# Atom-N.net
KiCad netlist of a schematic drawn in Altium Designer
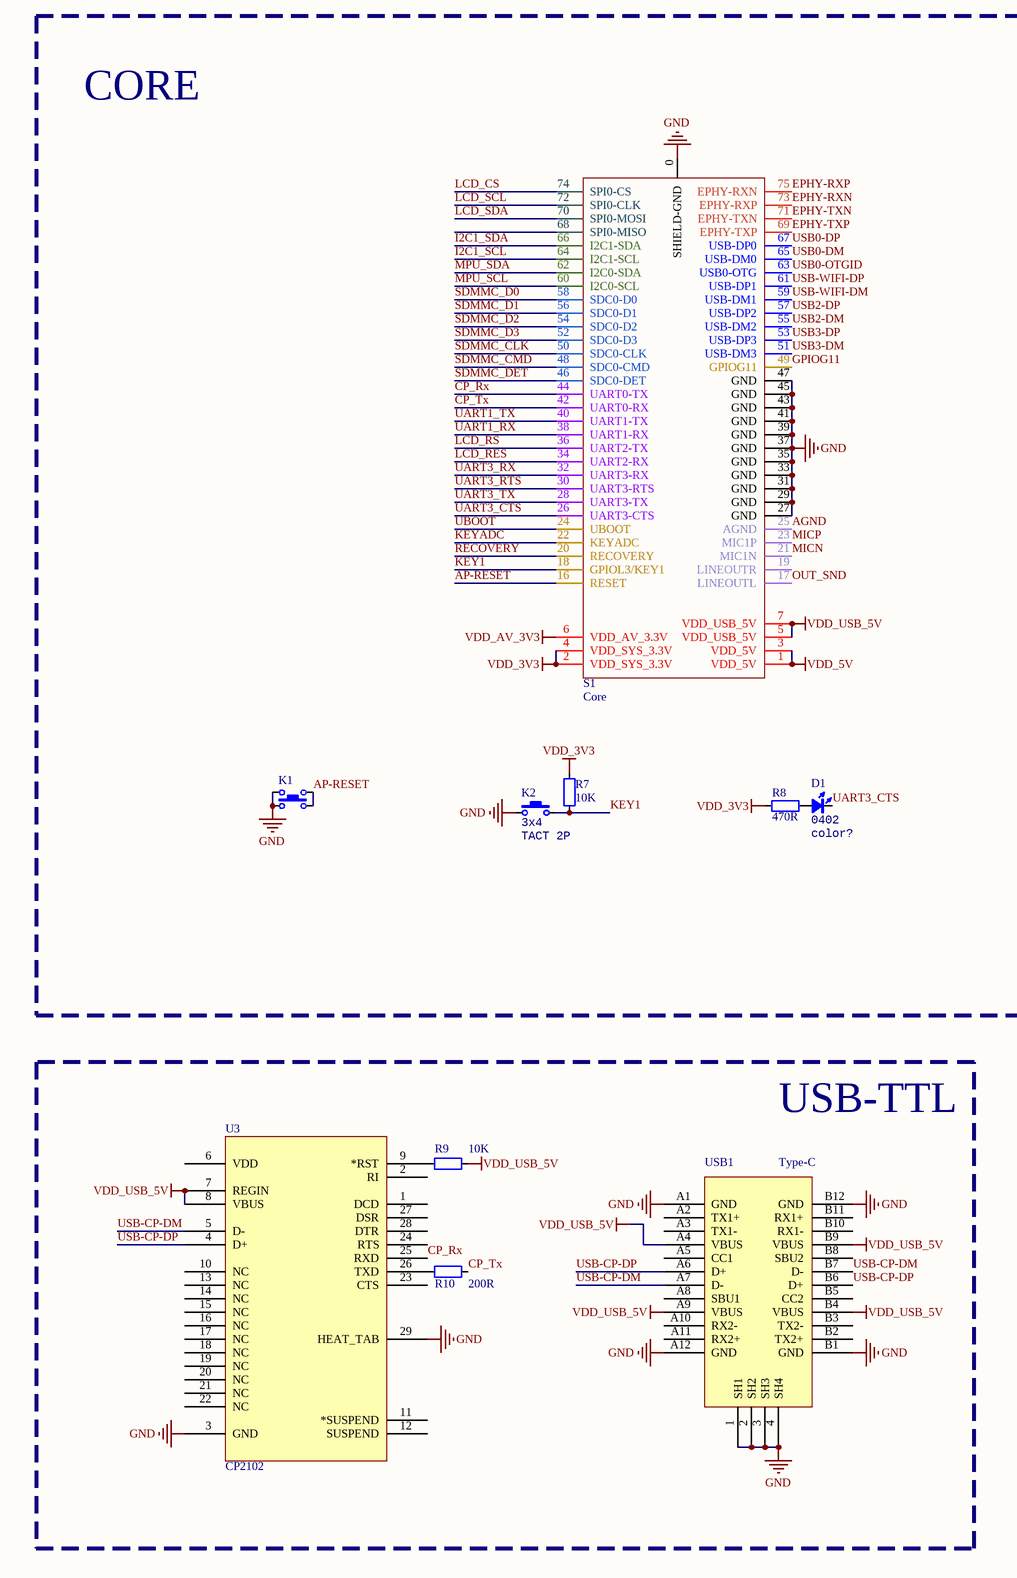
[diagram p0: Atom-N.SchDoc, left]
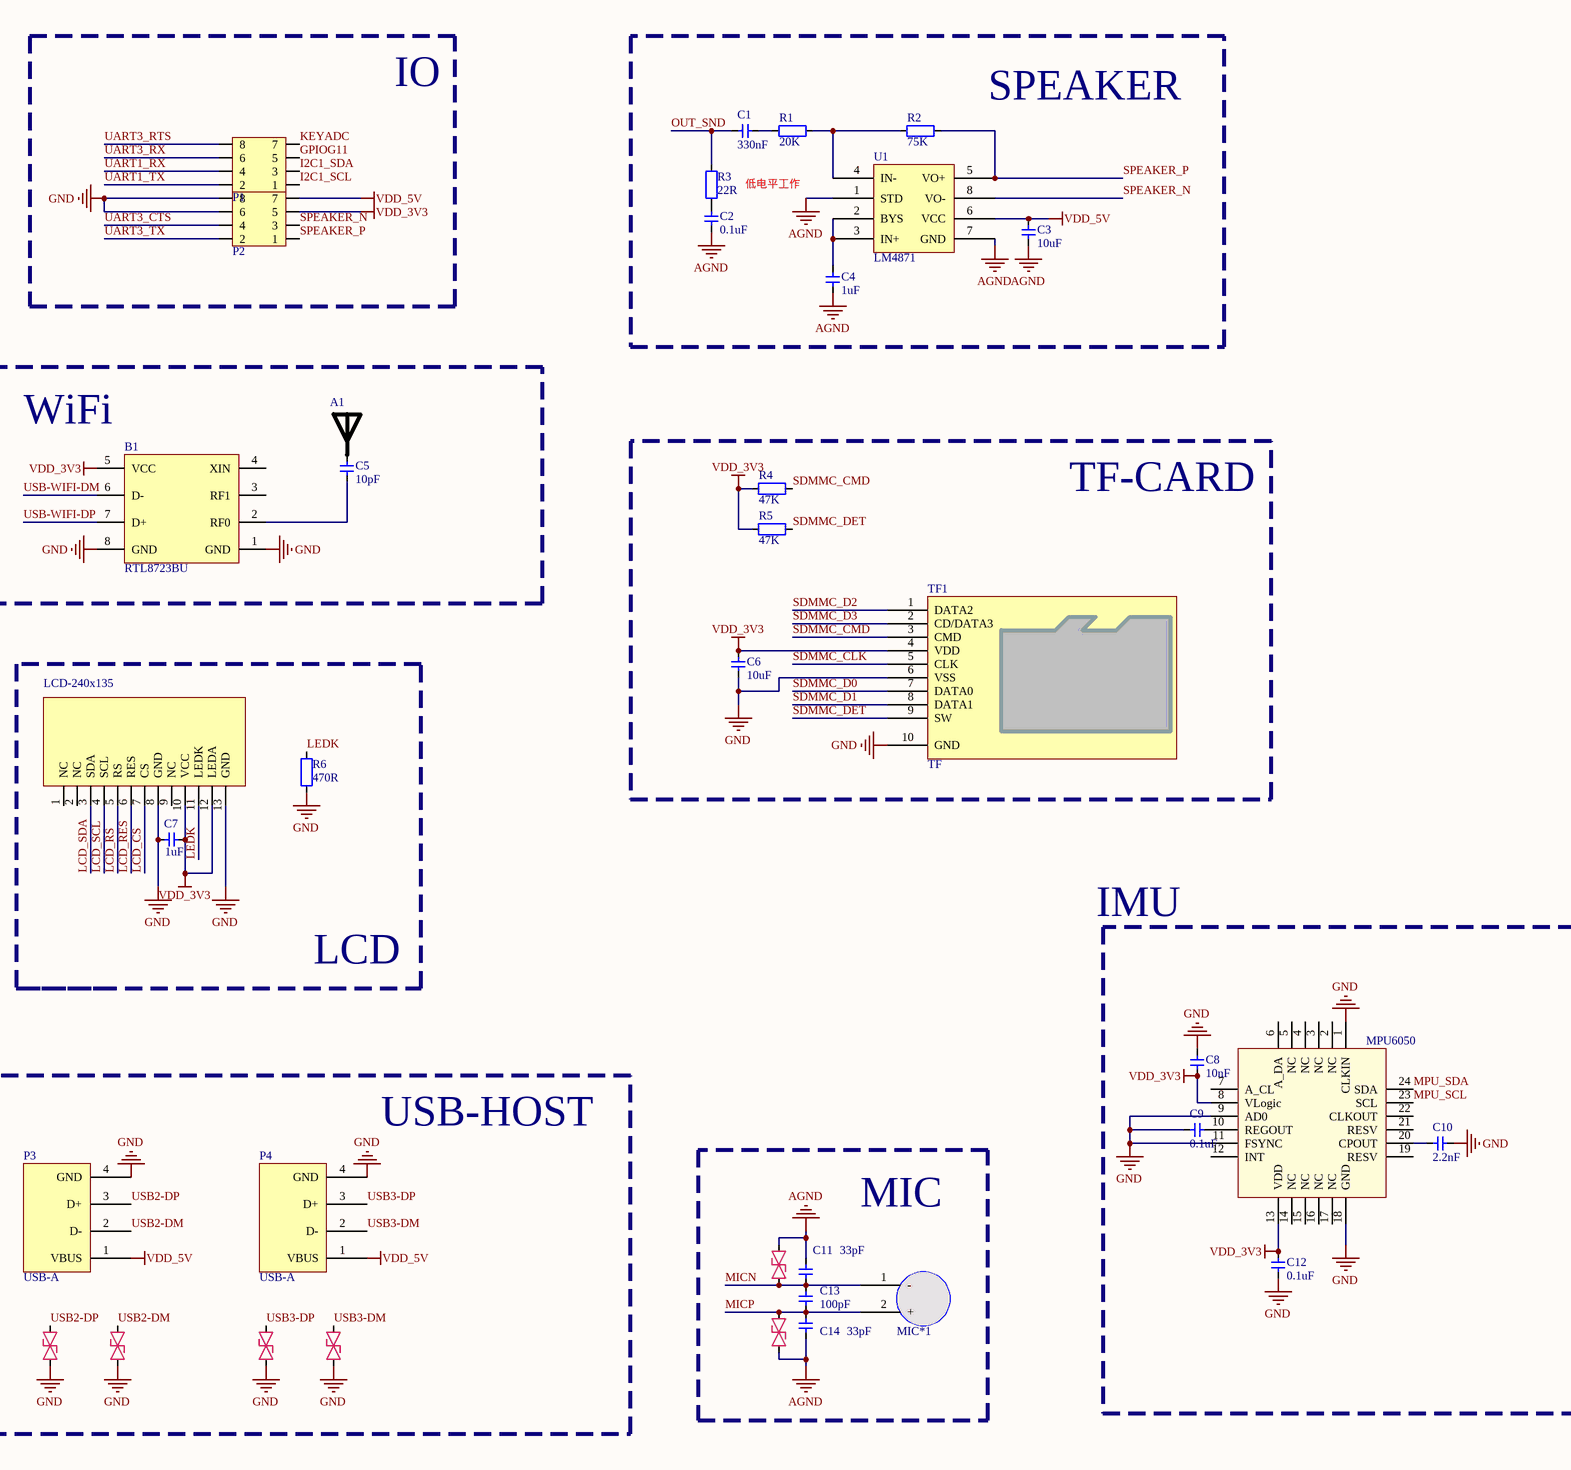
[diagram p1: Atom-N.SchDoc, right]

(export (version "E")
  (design (tool "Eeschema 10.0.6"))
  (components
    (comp (ref "1")
      (value "LCD-240x135")
      (footprint "LCD-240x135")
      (description "显示屏")
      (libsource (lib "MyPcbLib") (part "LCD-240x135"))
    )
    (comp (ref "A1")
      (value "RAINSUN")
      (footprint "ANT-Rainsun-AN5120")
      (libsource (lib "MyPcbLib") (part "ANT-Rainsun-AP5120"))
    )
    (comp (ref "B1")
      (value "RTL8723BU")
      (footprint "USB-WiFI-BT-RTL8723BU")
      (libsource (lib "MyPcbLib") (part "USB-WiFi-BT-RTL8723BU"))
    )
    (comp (ref "C1")
      (value "330nF")
      (footprint "0603-CAP")
      (description "Capacitor")
      (libsource (lib "MyPcbLib") (part "电容-0603"))
    )
    (comp (ref "C2")
      (value "0.1uF")
      (footprint "CAP_0402")
      (description "Capacitor")
      (libsource (lib "MyPcbLib") (part "电容-0402"))
    )
    (comp (ref "C3")
      (value "10uF")
      (footprint "CAP_0402")
      (description "Capacitor")
      (libsource (lib "MyPcbLib") (part "电容-0402"))
    )
    (comp (ref "C4")
      (value "1uF")
      (footprint "CAP_0402")
      (description "Capacitor")
      (libsource (lib "MyPcbLib") (part "电容-0402"))
    )
    (comp (ref "C5")
      (value "10pF")
      (footprint "CAP_0402")
      (description "Capacitor")
      (libsource (lib "MyPcbLib") (part "电容-0402"))
    )
    (comp (ref "C6")
      (value "10uF")
      (footprint "CAP_0402")
      (description "Capacitor")
      (libsource (lib "MyPcbLib") (part "电容-0402"))
    )
    (comp (ref "C7")
      (value "1uF")
      (footprint "CAP_0402")
      (description "Capacitor")
      (libsource (lib "MyPcbLib") (part "电容-0402"))
    )
    (comp (ref "C8")
      (value "10nF")
      (footprint "CAP_0402")
      (description "Capacitor")
      (libsource (lib "MyPcbLib") (part "电容-0402"))
    )
    (comp (ref "C9")
      (value "0.1uF")
      (footprint "CAP_0402")
      (description "Capacitor")
      (libsource (lib "MyPcbLib") (part "电容-0402"))
    )
    (comp (ref "C10")
      (value "2.2nF")
      (footprint "CAP_0402")
      (description "Capacitor")
      (libsource (lib "MyPcbLib") (part "电容-0402"))
    )
    (comp (ref "C11")
      (value "33pF")
      (footprint "CAP_0402")
      (description "Capacitor")
      (libsource (lib "MyPcbLib") (part "电容-0402"))
    )
    (comp (ref "C12")
      (value "0.1uF")
      (footprint "CAP_0402")
      (description "Capacitor")
      (libsource (lib "MyPcbLib") (part "电容-0402"))
    )
    (comp (ref "C13")
      (value "100pF")
      (footprint "CAP_0402")
      (description "Capacitor")
      (libsource (lib "MyPcbLib") (part "电容-0402"))
    )
    (comp (ref "C14")
      (value "33pF")
      (footprint "CAP_0402")
      (description "Capacitor")
      (libsource (lib "MyPcbLib") (part "电容-0402"))
    )
    (comp (ref "D1")
      (value "color?")
      (footprint "LED_0402_RED")
      (description "LED")
      (fields (field (name "TYPE") "0402"))
      (libsource (lib "KitSprout") (part "LED_0402"))
    )
    (comp (ref "ESD-1")
      (value "ESD-0402")
      (footprint "ESD-0402")
      (description "ESD")
      (libsource (lib "MyPcbLib") (part "ESD-0402"))
    )
    (comp (ref "ESD-2")
      (value "ESD-0402")
      (footprint "ESD-0402")
      (description "ESD")
      (libsource (lib "MyPcbLib") (part "ESD-0402"))
    )
    (comp (ref "ESD-3")
      (value "ESD-0402")
      (footprint "ESD-0402")
      (description "ESD")
      (libsource (lib "MyPcbLib") (part "ESD-0402"))
    )
    (comp (ref "ESD-4")
      (value "ESD-0402")
      (footprint "ESD-0402")
      (description "ESD")
      (libsource (lib "MyPcbLib") (part "ESD-0402"))
    )
    (comp (ref "ESD-5")
      (value "ESD-0402")
      (footprint "ESD-0402")
      (description "ESD")
      (libsource (lib "MyPcbLib") (part "ESD-0402"))
    )
    (comp (ref "ESD-6")
      (value "ESD-0402")
      (footprint "ESD-0402")
      (description "ESD")
      (libsource (lib "MyPcbLib") (part "ESD-0402"))
    )
    (comp (ref "K1")
      (value "TACT 4P")
      (footprint "ButtonTACT_3.5*3.55_90")
      (description "Button")
      (libsource (lib "KitSprout") (part "ButtonTACT"))
    )
    (comp (ref "K2")
      (value "3x4")
      (footprint "ButtonTACT_3x4x2_180")
      (description "Button")
      (fields (field (name "TYPE") "TACT 2P") (field (name "Comment") "TACT 2P"))
      (libsource (lib "KitSprout") (part "ButtonTACT_3x4x2_180"))
    )
    (comp (ref "MIC*1") (value "MIC*") (footprint "MIC-SMT") (libsource (lib "mLib") (part "MIC")))
    (comp (ref "P1")
      (value "HDR2x4_2.54")
      (footprint "HDR2X4_2.0_180H")
      (description "Header")
      (libsource (lib "mLib") (part "HDR2x4_2.54"))
    )
    (comp (ref "P2")
      (value "HDR2x4_2.54")
      (footprint "HDR2X4_2.0_180H")
      (description "Header")
      (libsource (lib "mLib") (part "HDR2x4_2.54"))
    )
    (comp (ref "P3") (value "USB-A") (footprint "USB-Short") (libsource (lib "MyPcbLib") (part "USB-A")))
    (comp (ref "P4") (value "USB-A") (footprint "USB-Short") (libsource (lib "MyPcbLib") (part "USB-A")))
    (comp (ref "R1")
      (value "20K")
      (footprint "RES_0402")
      (description "Resistor")
      (libsource (lib "") (part "电阻-0402_1"))
    )
    (comp (ref "R2")
      (value "75K")
      (footprint "RES_0402")
      (description "Resistor")
      (libsource (lib "") (part "电阻-0402_1"))
    )
    (comp (ref "R3")
      (value "22R")
      (footprint "RES_0402")
      (description "Resistor")
      (libsource (lib "") (part "电阻-0402_2"))
    )
    (comp (ref "R4")
      (value "47K")
      (footprint "RES_0402")
      (description "Resistor")
      (libsource (lib "") (part "电阻-0402_1"))
    )
    (comp (ref "R5")
      (value "47K")
      (footprint "RES_0402")
      (description "Resistor")
      (libsource (lib "") (part "电阻-0402_1"))
    )
    (comp (ref "R6")
      (value "470R")
      (footprint "RES_0402")
      (description "Resistor")
      (libsource (lib "") (part "电阻-0402_2"))
    )
    (comp (ref "R7")
      (value "10K")
      (footprint "RES_0402")
      (description "Resistor")
      (libsource (lib "") (part "电阻-0402_2"))
    )
    (comp (ref "R8")
      (value "470R")
      (footprint "RES_0402")
      (description "Resistor")
      (libsource (lib "MyPcbLib") (part "电阻-0402"))
    )
    (comp (ref "R9")
      (value "10K")
      (footprint "RES_0402")
      (description "Resistor")
      (libsource (lib "MyPcbLib") (part "电阻-0402"))
    )
    (comp (ref "R10")
      (value "200R")
      (footprint "RES_0402")
      (description "Resistor")
      (libsource (lib "MyPcbLib") (part "电阻-0402"))
    )
    (comp (ref "S1")
      (value "Core")
      (footprint "QUANTUM-QUARK-N")
      (libsource (lib "SOM") (part "Quantum-Quark-N"))
    )
    (comp (ref "TF1")
      (value "TF")
      (footprint "TF-SOCKET - short")
      (description "8脚自弹")
      (libsource (lib "MyPcbLib") (part "TF卡座"))
    )
    (comp (ref "U1") (value "LM4871") (footprint "MSOP-8") (libsource (lib "mLib") (part "LM4871")))
    (comp (ref "U2")
      (value "MPU6050")
      (footprint "QFN-24")
      (description "六轴传感器")
      (libsource (lib "mLib") (part "MPU6050"))
    )
    (comp (ref "U3")
      (value "CP2102")
      (footprint "QFN-28")
      (description "USB转TTL")
      (libsource (lib "mLib") (part "CP2102"))
    )
    (comp (ref "USB1")
      (value "Type-C")
      (footprint "Type-C-TOP")
      (libsource (lib "MyPcbLib") (part "USB-Type-C-TOP"))
    )
  )
  (nets
    (net (code "1") (name "/AP-RESET") (class "Default")
      (node (ref "K1") (pin "2") (pinfunction "2_2") (pintype "passive"))
      (node (ref "K1") (pin "4") (pinfunction "4_4") (pintype "passive"))
      (node (ref "S1") (pin "16") (pinfunction "RESET_16") (pintype "passive"))
    )
    (net (code "2") (name "/CP_Rx") (class "Default")
      (node (ref "S1") (pin "44") (pinfunction "UART0-TX_44") (pintype "passive"))
      (node (ref "U3") (pin "25") (pinfunction "RXD_25") (pintype "passive"))
    )
    (net (code "3") (name "/CP_Tx") (class "Default")
      (node (ref "R10") (pin "1") (pinfunction "1_1") (pintype "passive"))
      (node (ref "S1") (pin "42") (pinfunction "UART0-RX_42") (pintype "passive"))
    )
    (net (code "4") (name "/EPHY-RXN") (class "Default")
      (node (ref "S1") (pin "73") (pinfunction "EPHY-RXP_73") (pintype "passive"))
    )
    (net (code "5") (name "/EPHY-RXP") (class "Default")
      (node (ref "S1") (pin "75") (pinfunction "EPHY-RXN_75") (pintype "passive"))
    )
    (net (code "6") (name "/EPHY-TXN") (class "Default")
      (node (ref "S1") (pin "71") (pinfunction "EPHY-TXN_71") (pintype "passive"))
    )
    (net (code "7") (name "/EPHY-TXP") (class "Default")
      (node (ref "S1") (pin "69") (pinfunction "EPHY-TXP_69") (pintype "passive"))
    )
    (net (code "8") (name "/GPIOG11") (class "Default")
      (node (ref "P1") (pin "5") (pinfunction "5_5") (pintype "passive"))
      (node (ref "S1") (pin "49") (pinfunction "GPIOG11_49") (pintype "passive"))
    )
    (net (code "9") (name "/I2C1_SCL") (class "Default")
      (node (ref "P1") (pin "1") (pinfunction "1_1") (pintype "passive"))
      (node (ref "S1") (pin "64") (pinfunction "I2C1-SCL_64") (pintype "passive"))
    )
    (net (code "10") (name "/I2C1_SDA") (class "Default")
      (node (ref "P1") (pin "3") (pinfunction "3_3") (pintype "passive"))
      (node (ref "S1") (pin "66") (pinfunction "I2C1-SDA_66") (pintype "passive"))
    )
    (net (code "11") (name "/KEY1") (class "Default")
      (node (ref "K2") (pin "2") (pinfunction "2_2") (pintype "passive"))
      (node (ref "R7") (pin "1") (pinfunction "1_1") (pintype "passive"))
      (node (ref "S1") (pin "18") (pinfunction "GPIOL3/KEY1_18") (pintype "passive"))
    )
    (net (code "12") (name "/KEYADC") (class "Default")
      (node (ref "P1") (pin "7") (pinfunction "7_7") (pintype "passive"))
      (node (ref "S1") (pin "22") (pinfunction "KEYADC_22") (pintype "passive"))
    )
    (net (code "13") (name "/LCD_CS") (class "Default")
      (node (ref "1") (pin "7") (pinfunction "CS_7") (pintype "passive"))
      (node (ref "S1") (pin "74") (pinfunction "SPI0-CS_74") (pintype "passive"))
    )
    (net (code "14") (name "/LCD_RES") (class "Default")
      (node (ref "1") (pin "6") (pinfunction "RES_6") (pintype "passive"))
      (node (ref "S1") (pin "34") (pinfunction "UART2-RX_34") (pintype "passive"))
    )
    (net (code "15") (name "/LCD_RS") (class "Default")
      (node (ref "1") (pin "5") (pinfunction "RS_5") (pintype "passive"))
      (node (ref "S1") (pin "36") (pinfunction "UART2-TX_36") (pintype "passive"))
    )
    (net (code "16") (name "/LCD_SCL") (class "Default")
      (node (ref "1") (pin "4") (pinfunction "SCL_4") (pintype "passive"))
      (node (ref "S1") (pin "72") (pinfunction "SPI0-CLK_72") (pintype "passive"))
    )
    (net (code "17") (name "/LCD_SDA") (class "Default")
      (node (ref "1") (pin "3") (pinfunction "SDA_3") (pintype "passive"))
      (node (ref "S1") (pin "70") (pinfunction "SPI0-MOSI_70") (pintype "passive"))
    )
    (net (code "18") (name "/LEDK") (class "Default")
      (node (ref "1") (pin "11") (pinfunction "LEDK_11") (pintype "passive"))
      (node (ref "R6") (pin "2") (pinfunction "2_2") (pintype "passive"))
    )
    (net (code "19") (name "/MICN") (class "Default")
      (node (ref "C11") (pin "2") (pinfunction "2_2") (pintype "passive"))
      (node (ref "C13") (pin "2") (pinfunction "2_2") (pintype "passive"))
      (node (ref "ESD-1") (pin "1") (pinfunction "1_1") (pintype "passive"))
      (node (ref "MIC*1") (pin "1") (pinfunction "-_1") (pintype "passive"))
      (node (ref "S1") (pin "21") (pinfunction "MIC1N_21") (pintype "passive"))
    )
    (net (code "20") (name "/MICP") (class "Default")
      (node (ref "C13") (pin "1") (pinfunction "1_1") (pintype "passive"))
      (node (ref "C14") (pin "2") (pinfunction "2_2") (pintype "passive"))
      (node (ref "ESD-2") (pin "2") (pinfunction "2_2") (pintype "passive"))
      (node (ref "MIC*1") (pin "2") (pinfunction "+_2") (pintype "passive"))
      (node (ref "S1") (pin "23") (pinfunction "MIC1P_23") (pintype "passive"))
    )
    (net (code "21") (name "/MPU_SCL") (class "Default")
      (node (ref "S1") (pin "60") (pinfunction "I2C0-SCL_60") (pintype "passive"))
      (node (ref "U2") (pin "23") (pinfunction "SCL_23") (pintype "passive"))
    )
    (net (code "22") (name "/MPU_SDA") (class "Default")
      (node (ref "S1") (pin "62") (pinfunction "I2C0-SDA_62") (pintype "passive"))
      (node (ref "U2") (pin "24") (pinfunction "SDA_24") (pintype "passive"))
    )
    (net (code "23") (name "/OUT_SND") (class "Default")
      (node (ref "C1") (pin "2") (pinfunction "2_2") (pintype "passive"))
      (node (ref "R3") (pin "2") (pinfunction "2_2") (pintype "passive"))
      (node (ref "S1") (pin "17") (pinfunction "LINEOUTL_17") (pintype "passive"))
    )
    (net (code "24") (name "/RECOVERY") (class "Default")
      (node (ref "S1") (pin "20") (pinfunction "RECOVERY_20") (pintype "passive"))
    )
    (net (code "25") (name "/SDMMC_CLK") (class "Default")
      (node (ref "S1") (pin "50") (pinfunction "SDC0-CLK_50") (pintype "passive"))
      (node (ref "TF1") (pin "5") (pinfunction "CLK_5") (pintype "passive"))
    )
    (net (code "26") (name "/SDMMC_CMD") (class "Default")
      (node (ref "R4") (pin "2") (pinfunction "2_2") (pintype "passive"))
      (node (ref "S1") (pin "48") (pinfunction "SDC0-CMD_48") (pintype "passive"))
      (node (ref "TF1") (pin "3") (pinfunction "CMD_3") (pintype "passive"))
    )
    (net (code "27") (name "/SDMMC_D0") (class "Default")
      (node (ref "S1") (pin "58") (pinfunction "SDC0-D0_58") (pintype "passive"))
      (node (ref "TF1") (pin "7") (pinfunction "DATA0_7") (pintype "passive"))
    )
    (net (code "28") (name "/SDMMC_D1") (class "Default")
      (node (ref "S1") (pin "56") (pinfunction "SDC0-D1_56") (pintype "passive"))
      (node (ref "TF1") (pin "8") (pinfunction "DATA1_8") (pintype "passive"))
    )
    (net (code "29") (name "/SDMMC_D2") (class "Default")
      (node (ref "S1") (pin "54") (pinfunction "SDC0-D2_54") (pintype "passive"))
      (node (ref "TF1") (pin "1") (pinfunction "DATA2_1") (pintype "passive"))
    )
    (net (code "30") (name "/SDMMC_D3") (class "Default")
      (node (ref "S1") (pin "52") (pinfunction "SDC0-D3_52") (pintype "passive"))
      (node (ref "TF1") (pin "2") (pinfunction "CD/DATA3_2") (pintype "passive"))
    )
    (net (code "31") (name "/SDMMC_DET") (class "Default")
      (node (ref "R5") (pin "2") (pinfunction "2_2") (pintype "passive"))
      (node (ref "S1") (pin "46") (pinfunction "SDC0-DET_46") (pintype "passive"))
      (node (ref "TF1") (pin "9") (pinfunction "SW_9") (pintype "passive"))
    )
    (net (code "32") (name "/SPEAKER_N") (class "Default")
      (node (ref "P2") (pin "3") (pinfunction "3_3") (pintype "passive"))
      (node (ref "U1") (pin "8") (pinfunction "VO-_8") (pintype "passive"))
    )
    (net (code "33") (name "/SPEAKER_P") (class "Default")
      (node (ref "P2") (pin "1") (pinfunction "1_1") (pintype "passive"))
      (node (ref "R2") (pin "2") (pinfunction "2_2") (pintype "passive"))
      (node (ref "U1") (pin "5") (pinfunction "VO+_5") (pintype "passive"))
    )
    (net (code "34") (name "/UART1_RX") (class "Default")
      (node (ref "P1") (pin "4") (pinfunction "4_4") (pintype "passive"))
      (node (ref "S1") (pin "38") (pinfunction "UART1-RX_38") (pintype "passive"))
    )
    (net (code "35") (name "/UART1_TX") (class "Default")
      (node (ref "P1") (pin "2") (pinfunction "2_2") (pintype "passive"))
      (node (ref "S1") (pin "40") (pinfunction "UART1-TX_40") (pintype "passive"))
    )
    (net (code "36") (name "/UART3_CTS") (class "Default")
      (node (ref "D1") (pin "2") (pinfunction "K_2") (pintype "passive"))
      (node (ref "P2") (pin "4") (pinfunction "4_4") (pintype "passive"))
      (node (ref "S1") (pin "26") (pinfunction "UART3-CTS_26") (pintype "passive"))
    )
    (net (code "37") (name "/UART3_RTS") (class "Default")
      (node (ref "P1") (pin "8") (pinfunction "8_8") (pintype "passive"))
      (node (ref "S1") (pin "30") (pinfunction "UART3-RTS_30") (pintype "passive"))
    )
    (net (code "38") (name "/UART3_RX") (class "Default")
      (node (ref "P1") (pin "6") (pinfunction "6_6") (pintype "passive"))
      (node (ref "S1") (pin "32") (pinfunction "UART3-RX_32") (pintype "passive"))
    )
    (net (code "39") (name "/UART3_TX") (class "Default")
      (node (ref "P2") (pin "2") (pinfunction "2_2") (pintype "passive"))
      (node (ref "S1") (pin "28") (pinfunction "UART3-TX_28") (pintype "passive"))
    )
    (net (code "40") (name "/UBOOT") (class "Default")
      (node (ref "S1") (pin "24") (pinfunction "UBOOT_24") (pintype "passive"))
    )
    (net (code "41") (name "/USB-CP-DM") (class "Default")
      (node (ref "U3") (pin "5") (pinfunction "D-_5") (pintype "passive"))
      (node (ref "USB1") (pin "A7") (pinfunction "D-_A7") (pintype "passive"))
      (node (ref "USB1") (pin "B7") (pinfunction "D-_B7") (pintype "passive"))
    )
    (net (code "42") (name "/USB-CP-DP") (class "Default")
      (node (ref "U3") (pin "4") (pinfunction "D+_4") (pintype "passive"))
      (node (ref "USB1") (pin "A6") (pinfunction "D+_A6") (pintype "passive"))
      (node (ref "USB1") (pin "B6") (pinfunction "D+_B6") (pintype "passive"))
    )
    (net (code "43") (name "/USB-WIFI-DM") (class "Default")
      (node (ref "B1") (pin "6") (pinfunction "D-_6") (pintype "passive"))
      (node (ref "S1") (pin "59") (pinfunction "USB-DM1_59") (pintype "passive"))
    )
    (net (code "44") (name "/USB-WIFI-DP") (class "Default")
      (node (ref "B1") (pin "7") (pinfunction "D+_7") (pintype "passive"))
      (node (ref "S1") (pin "61") (pinfunction "USB-DP1_61") (pintype "passive"))
    )
    (net (code "45") (name "/USB0-DM") (class "Default")
      (node (ref "S1") (pin "65") (pinfunction "USB-DM0_65") (pintype "passive"))
    )
    (net (code "46") (name "/USB0-DP") (class "Default")
      (node (ref "S1") (pin "67") (pinfunction "USB-DP0_67") (pintype "passive"))
    )
    (net (code "47") (name "/USB0-OTGID") (class "Default")
      (node (ref "S1") (pin "63") (pinfunction "USB0-OTG_63") (pintype "passive"))
    )
    (net (code "48") (name "/USB2-DM") (class "Default")
      (node (ref "ESD-4") (pin "2") (pinfunction "2_2") (pintype "passive"))
      (node (ref "P3") (pin "2") (pinfunction "D-_2") (pintype "passive"))
      (node (ref "S1") (pin "55") (pinfunction "USB-DM2_55") (pintype "passive"))
    )
    (net (code "49") (name "/USB2-DP") (class "Default")
      (node (ref "ESD-3") (pin "2") (pinfunction "2_2") (pintype "passive"))
      (node (ref "P3") (pin "3") (pinfunction "D+_3") (pintype "passive"))
      (node (ref "S1") (pin "57") (pinfunction "USB-DP2_57") (pintype "passive"))
    )
    (net (code "50") (name "/USB3-DM") (class "Default")
      (node (ref "ESD-6") (pin "2") (pinfunction "2_2") (pintype "passive"))
      (node (ref "P4") (pin "2") (pinfunction "D-_2") (pintype "passive"))
      (node (ref "S1") (pin "51") (pinfunction "USB-DM3_51") (pintype "passive"))
    )
    (net (code "51") (name "/USB3-DP") (class "Default")
      (node (ref "ESD-5") (pin "2") (pinfunction "2_2") (pintype "passive"))
      (node (ref "P4") (pin "3") (pinfunction "D+_3") (pintype "passive"))
      (node (ref "S1") (pin "53") (pinfunction "USB-DP3_53") (pintype "passive"))
    )
    (net (code "52") (name "AGND") (class "Default")
      (node (ref "C11") (pin "1") (pinfunction "1_1") (pintype "passive"))
      (node (ref "C14") (pin "1") (pinfunction "1_1") (pintype "passive"))
      (node (ref "C2") (pin "1") (pinfunction "1_1") (pintype "passive"))
      (node (ref "C3") (pin "1") (pinfunction "1_1") (pintype "passive"))
      (node (ref "C4") (pin "1") (pinfunction "1_1") (pintype "passive"))
      (node (ref "ESD-1") (pin "2") (pinfunction "2_2") (pintype "passive"))
      (node (ref "ESD-2") (pin "1") (pinfunction "1_1") (pintype "passive"))
      (node (ref "S1") (pin "25") (pinfunction "AGND_25") (pintype "passive"))
      (node (ref "U1") (pin "1") (pinfunction "STD_1") (pintype "passive"))
      (node (ref "U1") (pin "7") (pinfunction "GND_7") (pintype "passive"))
    )
    (net (code "53") (name "GND") (class "Default")
      (node (ref "1") (pin "13") (pinfunction "GND_13") (pintype "passive"))
      (node (ref "1") (pin "8") (pinfunction "GND_8") (pintype "passive"))
      (node (ref "B1") (pin "1") (pinfunction "GND_1") (pintype "passive"))
      (node (ref "B1") (pin "8") (pinfunction "GND_8") (pintype "passive"))
      (node (ref "C10") (pin "1") (pinfunction "1_1") (pintype "passive"))
      (node (ref "C12") (pin "1") (pinfunction "1_1") (pintype "passive"))
      (node (ref "C6") (pin "1") (pinfunction "1_1") (pintype "passive"))
      (node (ref "C7") (pin "2") (pinfunction "2_2") (pintype "passive"))
      (node (ref "C8") (pin "2") (pinfunction "2_2") (pintype "passive"))
      (node (ref "C9") (pin "2") (pinfunction "2_2") (pintype "passive"))
      (node (ref "ESD-3") (pin "1") (pinfunction "1_1") (pintype "passive"))
      (node (ref "ESD-4") (pin "1") (pinfunction "1_1") (pintype "passive"))
      (node (ref "ESD-5") (pin "1") (pinfunction "1_1") (pintype "passive"))
      (node (ref "ESD-6") (pin "1") (pinfunction "1_1") (pintype "passive"))
      (node (ref "K1") (pin "1") (pinfunction "1_1") (pintype "passive"))
      (node (ref "K1") (pin "3") (pinfunction "3_3") (pintype "passive"))
      (node (ref "K2") (pin "1") (pinfunction "1_1") (pintype "passive"))
      (node (ref "P2") (pin "6") (pinfunction "6_6") (pintype "passive"))
      (node (ref "P2") (pin "8") (pinfunction "8_8") (pintype "passive"))
      (node (ref "P3") (pin "4") (pinfunction "GND_4") (pintype "passive"))
      (node (ref "P4") (pin "4") (pinfunction "GND_4") (pintype "passive"))
      (node (ref "R6") (pin "1") (pinfunction "1_1") (pintype "passive"))
      (node (ref "S1") (pin "27") (pinfunction "GND_27") (pintype "passive"))
      (node (ref "S1") (pin "29") (pinfunction "GND_29") (pintype "passive"))
      (node (ref "S1") (pin "31") (pinfunction "GND_31") (pintype "passive"))
      (node (ref "S1") (pin "33") (pinfunction "GND_33") (pintype "passive"))
      (node (ref "S1") (pin "35") (pinfunction "GND_35") (pintype "passive"))
      (node (ref "S1") (pin "37") (pinfunction "GND_37") (pintype "passive"))
      (node (ref "S1") (pin "39") (pinfunction "GND_39") (pintype "passive"))
      (node (ref "S1") (pin "41") (pinfunction "GND_41") (pintype "passive"))
      (node (ref "S1") (pin "43") (pinfunction "GND_43") (pintype "passive"))
      (node (ref "S1") (pin "45") (pinfunction "GND_45") (pintype "passive"))
      (node (ref "S1") (pin "47") (pinfunction "GND_47") (pintype "passive"))
      (node (ref "TF1") (pin "10") (pinfunction "GND_10") (pintype "passive"))
      (node (ref "TF1") (pin "6") (pinfunction "VSS_6") (pintype "passive"))
      (node (ref "U2") (pin "1") (pinfunction "CLKIN_1") (pintype "passive"))
      (node (ref "U2") (pin "11") (pinfunction "FSYNC_11") (pintype "passive"))
      (node (ref "U2") (pin "18") (pinfunction "GND_18") (pintype "passive"))
      (node (ref "U2") (pin "9") (pinfunction "AD0_9") (pintype "passive"))
      (node (ref "U3") (pin "29") (pinfunction "HEAT_TAB_29") (pintype "passive"))
      (node (ref "U3") (pin "3") (pinfunction "GND_3") (pintype "passive"))
      (node (ref "USB1") (pin "1") (pinfunction "SH1_1") (pintype "passive"))
      (node (ref "USB1") (pin "2") (pinfunction "SH2_2") (pintype "passive"))
      (node (ref "USB1") (pin "3") (pinfunction "SH3_3") (pintype "passive"))
      (node (ref "USB1") (pin "4") (pinfunction "SH4_4") (pintype "passive"))
      (node (ref "USB1") (pin "A1") (pinfunction "GND_A1") (pintype "passive"))
      (node (ref "USB1") (pin "A12") (pinfunction "GND_A12") (pintype "passive"))
      (node (ref "USB1") (pin "B1") (pinfunction "GND_B1") (pintype "passive"))
      (node (ref "USB1") (pin "B12") (pinfunction "GND_B12") (pintype "passive"))
    )
    (net (code "54") (name "Net-(A1-Pad1)") (class "Default")
      (node (ref "A1") (pin "1") (pinfunction "1_1") (pintype "passive"))
      (node (ref "C5") (pin "1") (pinfunction "1_1") (pintype "passive"))
    )
    (net (code "55") (name "Net-(B1-RF0)") (class "Default")
      (node (ref "B1") (pin "2") (pinfunction "RF0_2") (pintype "passive"))
      (node (ref "C5") (pin "2") (pinfunction "2_2") (pintype "passive"))
    )
    (net (code "56") (name "Net-(C1-Pad1)") (class "Default")
      (node (ref "C1") (pin "1") (pinfunction "1_1") (pintype "passive"))
      (node (ref "R1") (pin "1") (pinfunction "1_1") (pintype "passive"))
    )
    (net (code "57") (name "Net-(C2-Pad2)") (class "Default")
      (node (ref "C2") (pin "2") (pinfunction "2_2") (pintype "passive"))
      (node (ref "R3") (pin "1") (pinfunction "1_1") (pintype "passive"))
    )
    (net (code "58") (name "Net-(D1-A)") (class "Default")
      (node (ref "D1") (pin "1") (pinfunction "A_1") (pintype "passive"))
      (node (ref "R8") (pin "1") (pinfunction "1_1") (pintype "passive"))
    )
    (net (code "59") (name "Net-(U1-BYS)") (class "Default")
      (node (ref "C4") (pin "2") (pinfunction "2_2") (pintype "passive"))
      (node (ref "U1") (pin "2") (pinfunction "BYS_2") (pintype "passive"))
      (node (ref "U1") (pin "3") (pinfunction "IN+_3") (pintype "passive"))
    )
    (net (code "60") (name "Net-(U1-IN-)") (class "Default")
      (node (ref "R1") (pin "2") (pinfunction "2_2") (pintype "passive"))
      (node (ref "R2") (pin "1") (pinfunction "1_1") (pintype "passive"))
      (node (ref "U1") (pin "4") (pinfunction "IN-_4") (pintype "passive"))
    )
    (net (code "61") (name "Net-(U2-CPOUT)") (class "Default")
      (node (ref "C10") (pin "2") (pinfunction "2_2") (pintype "passive"))
      (node (ref "U2") (pin "20") (pinfunction "CPOUT_20") (pintype "passive"))
    )
    (net (code "62") (name "Net-(U2-REGOUT)") (class "Default")
      (node (ref "C9") (pin "1") (pinfunction "1_1") (pintype "passive"))
      (node (ref "U2") (pin "10") (pinfunction "REGOUT_10") (pintype "passive"))
    )
    (net (code "63") (name "Net-(U3-*RST)") (class "Default")
      (node (ref "R9") (pin "2") (pinfunction "2_2") (pintype "passive"))
      (node (ref "U3") (pin "9") (pinfunction "*RST_9") (pintype "passive"))
    )
    (net (code "64") (name "Net-(U3-TXD)") (class "Default")
      (node (ref "R10") (pin "2") (pinfunction "2_2") (pintype "passive"))
      (node (ref "U3") (pin "26") (pinfunction "TXD_26") (pintype "passive"))
    )
    (net (code "65") (name "VDD_3V3") (class "Default")
      (node (ref "1") (pin "10") (pinfunction "VCC_10") (pintype "passive"))
      (node (ref "1") (pin "12") (pinfunction "LEDA_12") (pintype "passive"))
      (node (ref "B1") (pin "5") (pinfunction "VCC_5") (pintype "passive"))
      (node (ref "C12") (pin "2") (pinfunction "2_2") (pintype "passive"))
      (node (ref "C6") (pin "2") (pinfunction "2_2") (pintype "passive"))
      (node (ref "C7") (pin "1") (pinfunction "1_1") (pintype "passive"))
      (node (ref "C8") (pin "1") (pinfunction "1_1") (pintype "passive"))
      (node (ref "P2") (pin "5") (pinfunction "5_5") (pintype "passive"))
      (node (ref "R4") (pin "1") (pinfunction "1_1") (pintype "passive"))
      (node (ref "R5") (pin "1") (pinfunction "1_1") (pintype "passive"))
      (node (ref "R7") (pin "2") (pinfunction "2_2") (pintype "passive"))
      (node (ref "R8") (pin "2") (pinfunction "2_2") (pintype "passive"))
      (node (ref "S1") (pin "2") (pinfunction "VDD_SYS_3.3V_2") (pintype "passive"))
      (node (ref "S1") (pin "4") (pinfunction "VDD_SYS_3.3V_4") (pintype "passive"))
      (node (ref "TF1") (pin "4") (pinfunction "VDD_4") (pintype "passive"))
      (node (ref "U2") (pin "13") (pinfunction "VDD_13") (pintype "passive"))
      (node (ref "U2") (pin "8") (pinfunction "VLogic_8") (pintype "passive"))
    )
    (net (code "66") (name "VDD_5V") (class "Default")
      (node (ref "C3") (pin "2") (pinfunction "2_2") (pintype "passive"))
      (node (ref "P2") (pin "7") (pinfunction "7_7") (pintype "passive"))
      (node (ref "P3") (pin "1") (pinfunction "VBUS_1") (pintype "passive"))
      (node (ref "P4") (pin "1") (pinfunction "VBUS_1") (pintype "passive"))
      (node (ref "S1") (pin "1") (pinfunction "VDD_5V_1") (pintype "passive"))
      (node (ref "S1") (pin "3") (pinfunction "VDD_5V_3") (pintype "passive"))
      (node (ref "U1") (pin "6") (pinfunction "VCC_6") (pintype "passive"))
    )
    (net (code "67") (name "VDD_AV_3V3") (class "Default")
      (node (ref "S1") (pin "6") (pinfunction "VDD_AV_3.3V_6") (pintype "passive"))
    )
    (net (code "68") (name "VDD_USB_5V") (class "Default")
      (node (ref "R9") (pin "1") (pinfunction "1_1") (pintype "passive"))
      (node (ref "S1") (pin "5") (pinfunction "VDD_USB_5V_5") (pintype "passive"))
      (node (ref "S1") (pin "7") (pinfunction "VDD_USB_5V_7") (pintype "passive"))
      (node (ref "U3") (pin "7") (pinfunction "REGIN_7") (pintype "passive"))
      (node (ref "U3") (pin "8") (pinfunction "VBUS_8") (pintype "passive"))
      (node (ref "USB1") (pin "A4") (pinfunction "VBUS_A4") (pintype "passive"))
      (node (ref "USB1") (pin "A9") (pinfunction "VBUS_A9") (pintype "passive"))
      (node (ref "USB1") (pin "B4") (pinfunction "VBUS_B4") (pintype "passive"))
      (node (ref "USB1") (pin "B9") (pinfunction "VBUS_B9") (pintype "passive"))
    )
    (net (code "69") (name "unconnected-(1-NC-Pad1)") (class "Default")
      (node (ref "1") (pin "1") (pinfunction "NC_1") (pintype "passive"))
    )
    (net (code "70") (name "unconnected-(1-NC-Pad2)") (class "Default")
      (node (ref "1") (pin "2") (pinfunction "NC_2") (pintype "passive"))
    )
    (net (code "71") (name "unconnected-(1-NC-Pad9)") (class "Default")
      (node (ref "1") (pin "9") (pinfunction "NC_9") (pintype "passive"))
    )
    (net (code "72") (name "unconnected-(B1-RF1-Pad3)") (class "Default")
      (node (ref "B1") (pin "3") (pinfunction "RF1_3") (pintype "passive"))
    )
    (net (code "73") (name "unconnected-(B1-XIN-Pad4)") (class "Default")
      (node (ref "B1") (pin "4") (pinfunction "XIN_4") (pintype "passive"))
    )
    (net (code "74") (name "unconnected-(S1-LINEOUTR-Pad19)") (class "Default")
      (node (ref "S1") (pin "19") (pinfunction "LINEOUTR_19") (pintype "passive"))
    )
    (net (code "75") (name "unconnected-(S1-SHIELD-GND-Pad0)") (class "Default")
      (node (ref "S1") (pin "0") (pinfunction "SHIELD-GND_0") (pintype "passive"))
    )
    (net (code "76") (name "unconnected-(S1-SPI0-MISO-Pad68)") (class "Default")
      (node (ref "S1") (pin "68") (pinfunction "SPI0-MISO_68") (pintype "passive"))
    )
    (net (code "77") (name "unconnected-(U2-A_CL-Pad7)") (class "Default")
      (node (ref "U2") (pin "7") (pinfunction "A_CL_7") (pintype "passive"))
    )
    (net (code "78") (name "unconnected-(U2-A_DA-Pad6)") (class "Default")
      (node (ref "U2") (pin "6") (pinfunction "A_DA_6") (pintype "passive"))
    )
    (net (code "79") (name "unconnected-(U2-CLKOUT-Pad22)") (class "Default")
      (node (ref "U2") (pin "22") (pinfunction "CLKOUT_22") (pintype "passive"))
    )
    (net (code "80") (name "unconnected-(U2-INT-Pad12)") (class "Default")
      (node (ref "U2") (pin "12") (pinfunction "INT_12") (pintype "passive"))
    )
    (net (code "81") (name "unconnected-(U2-NC-Pad2)") (class "Default")
      (node (ref "U2") (pin "2") (pinfunction "NC_2") (pintype "passive"))
    )
    (net (code "82") (name "unconnected-(U2-NC-Pad3)") (class "Default")
      (node (ref "U2") (pin "3") (pinfunction "NC_3") (pintype "passive"))
    )
    (net (code "83") (name "unconnected-(U2-NC-Pad4)") (class "Default")
      (node (ref "U2") (pin "4") (pinfunction "NC_4") (pintype "passive"))
    )
    (net (code "84") (name "unconnected-(U2-NC-Pad5)") (class "Default")
      (node (ref "U2") (pin "5") (pinfunction "NC_5") (pintype "passive"))
    )
    (net (code "85") (name "unconnected-(U2-NC-Pad14)") (class "Default")
      (node (ref "U2") (pin "14") (pinfunction "NC_14") (pintype "passive"))
    )
    (net (code "86") (name "unconnected-(U2-NC-Pad15)") (class "Default")
      (node (ref "U2") (pin "15") (pinfunction "NC_15") (pintype "passive"))
    )
    (net (code "87") (name "unconnected-(U2-NC-Pad16)") (class "Default")
      (node (ref "U2") (pin "16") (pinfunction "NC_16") (pintype "passive"))
    )
    (net (code "88") (name "unconnected-(U2-NC-Pad17)") (class "Default")
      (node (ref "U2") (pin "17") (pinfunction "NC_17") (pintype "passive"))
    )
    (net (code "89") (name "unconnected-(U2-RESV-Pad19)") (class "Default")
      (node (ref "U2") (pin "19") (pinfunction "RESV_19") (pintype "passive"))
    )
    (net (code "90") (name "unconnected-(U2-RESV-Pad21)") (class "Default")
      (node (ref "U2") (pin "21") (pinfunction "RESV_21") (pintype "passive"))
    )
    (net (code "91") (name "unconnected-(U3-*SUSPEND-Pad11)") (class "Default")
      (node (ref "U3") (pin "11") (pinfunction "*SUSPEND_11") (pintype "passive"))
    )
    (net (code "92") (name "unconnected-(U3-CTS-Pad23)") (class "Default")
      (node (ref "U3") (pin "23") (pinfunction "CTS_23") (pintype "passive"))
    )
    (net (code "93") (name "unconnected-(U3-DCD-Pad1)") (class "Default")
      (node (ref "U3") (pin "1") (pinfunction "DCD_1") (pintype "passive"))
    )
    (net (code "94") (name "unconnected-(U3-DSR-Pad27)") (class "Default")
      (node (ref "U3") (pin "27") (pinfunction "DSR_27") (pintype "passive"))
    )
    (net (code "95") (name "unconnected-(U3-DTR-Pad28)") (class "Default")
      (node (ref "U3") (pin "28") (pinfunction "DTR_28") (pintype "passive"))
    )
    (net (code "96") (name "unconnected-(U3-NC-Pad10)") (class "Default")
      (node (ref "U3") (pin "10") (pinfunction "NC_10") (pintype "passive"))
    )
    (net (code "97") (name "unconnected-(U3-NC-Pad13)") (class "Default")
      (node (ref "U3") (pin "13") (pinfunction "NC_13") (pintype "passive"))
    )
    (net (code "98") (name "unconnected-(U3-NC-Pad14)") (class "Default")
      (node (ref "U3") (pin "14") (pinfunction "NC_14") (pintype "passive"))
    )
    (net (code "99") (name "unconnected-(U3-NC-Pad15)") (class "Default")
      (node (ref "U3") (pin "15") (pinfunction "NC_15") (pintype "passive"))
    )
    (net (code "100") (name "unconnected-(U3-NC-Pad16)") (class "Default")
      (node (ref "U3") (pin "16") (pinfunction "NC_16") (pintype "passive"))
    )
    (net (code "101") (name "unconnected-(U3-NC-Pad17)") (class "Default")
      (node (ref "U3") (pin "17") (pinfunction "NC_17") (pintype "passive"))
    )
    (net (code "102") (name "unconnected-(U3-NC-Pad18)") (class "Default")
      (node (ref "U3") (pin "18") (pinfunction "NC_18") (pintype "passive"))
    )
    (net (code "103") (name "unconnected-(U3-NC-Pad19)") (class "Default")
      (node (ref "U3") (pin "19") (pinfunction "NC_19") (pintype "passive"))
    )
    (net (code "104") (name "unconnected-(U3-NC-Pad20)") (class "Default")
      (node (ref "U3") (pin "20") (pinfunction "NC_20") (pintype "passive"))
    )
    (net (code "105") (name "unconnected-(U3-NC-Pad21)") (class "Default")
      (node (ref "U3") (pin "21") (pinfunction "NC_21") (pintype "passive"))
    )
    (net (code "106") (name "unconnected-(U3-NC-Pad22)") (class "Default")
      (node (ref "U3") (pin "22") (pinfunction "NC_22") (pintype "passive"))
    )
    (net (code "107") (name "unconnected-(U3-RI-Pad2)") (class "Default")
      (node (ref "U3") (pin "2") (pinfunction "RI_2") (pintype "passive"))
    )
    (net (code "108") (name "unconnected-(U3-RTS-Pad24)") (class "Default")
      (node (ref "U3") (pin "24") (pinfunction "RTS_24") (pintype "passive"))
    )
    (net (code "109") (name "unconnected-(U3-SUSPEND-Pad12)") (class "Default")
      (node (ref "U3") (pin "12") (pinfunction "SUSPEND_12") (pintype "passive"))
    )
    (net (code "110") (name "unconnected-(U3-VDD-Pad6)") (class "Default")
      (node (ref "U3") (pin "6") (pinfunction "VDD_6") (pintype "passive"))
    )
    (net (code "111") (name "unconnected-(USB1-CC1-PadA5)") (class "Default")
      (node (ref "USB1") (pin "A5") (pinfunction "CC1_A5") (pintype "passive"))
    )
    (net (code "112") (name "unconnected-(USB1-CC2-PadB5)") (class "Default")
      (node (ref "USB1") (pin "B5") (pinfunction "CC2_B5") (pintype "passive"))
    )
    (net (code "113") (name "unconnected-(USB1-RX1+-PadB11)") (class "Default")
      (node (ref "USB1") (pin "B11") (pinfunction "RX1+_B11") (pintype "passive"))
    )
    (net (code "114") (name "unconnected-(USB1-RX1--PadB10)") (class "Default")
      (node (ref "USB1") (pin "B10") (pinfunction "RX1-_B10") (pintype "passive"))
    )
    (net (code "115") (name "unconnected-(USB1-RX2+-PadA11)") (class "Default")
      (node (ref "USB1") (pin "A11") (pinfunction "RX2+_A11") (pintype "passive"))
    )
    (net (code "116") (name "unconnected-(USB1-RX2--PadA10)") (class "Default")
      (node (ref "USB1") (pin "A10") (pinfunction "RX2-_A10") (pintype "passive"))
    )
    (net (code "117") (name "unconnected-(USB1-SBU1-PadA8)") (class "Default")
      (node (ref "USB1") (pin "A8") (pinfunction "SBU1_A8") (pintype "passive"))
    )
    (net (code "118") (name "unconnected-(USB1-SBU2-PadB8)") (class "Default")
      (node (ref "USB1") (pin "B8") (pinfunction "SBU2_B8") (pintype "passive"))
    )
    (net (code "119") (name "unconnected-(USB1-TX1+-PadA2)") (class "Default")
      (node (ref "USB1") (pin "A2") (pinfunction "TX1+_A2") (pintype "passive"))
    )
    (net (code "120") (name "unconnected-(USB1-TX1--PadA3)") (class "Default")
      (node (ref "USB1") (pin "A3") (pinfunction "TX1-_A3") (pintype "passive"))
    )
    (net (code "121") (name "unconnected-(USB1-TX2+-PadB2)") (class "Default")
      (node (ref "USB1") (pin "B2") (pinfunction "TX2+_B2") (pintype "passive"))
    )
    (net (code "122") (name "unconnected-(USB1-TX2--PadB3)") (class "Default")
      (node (ref "USB1") (pin "B3") (pinfunction "TX2-_B3") (pintype "passive"))
    )
  )
)
